# VFD-IV-26-T3-5x7.net
KiCad netlist of a schematic drawn in EAGLE
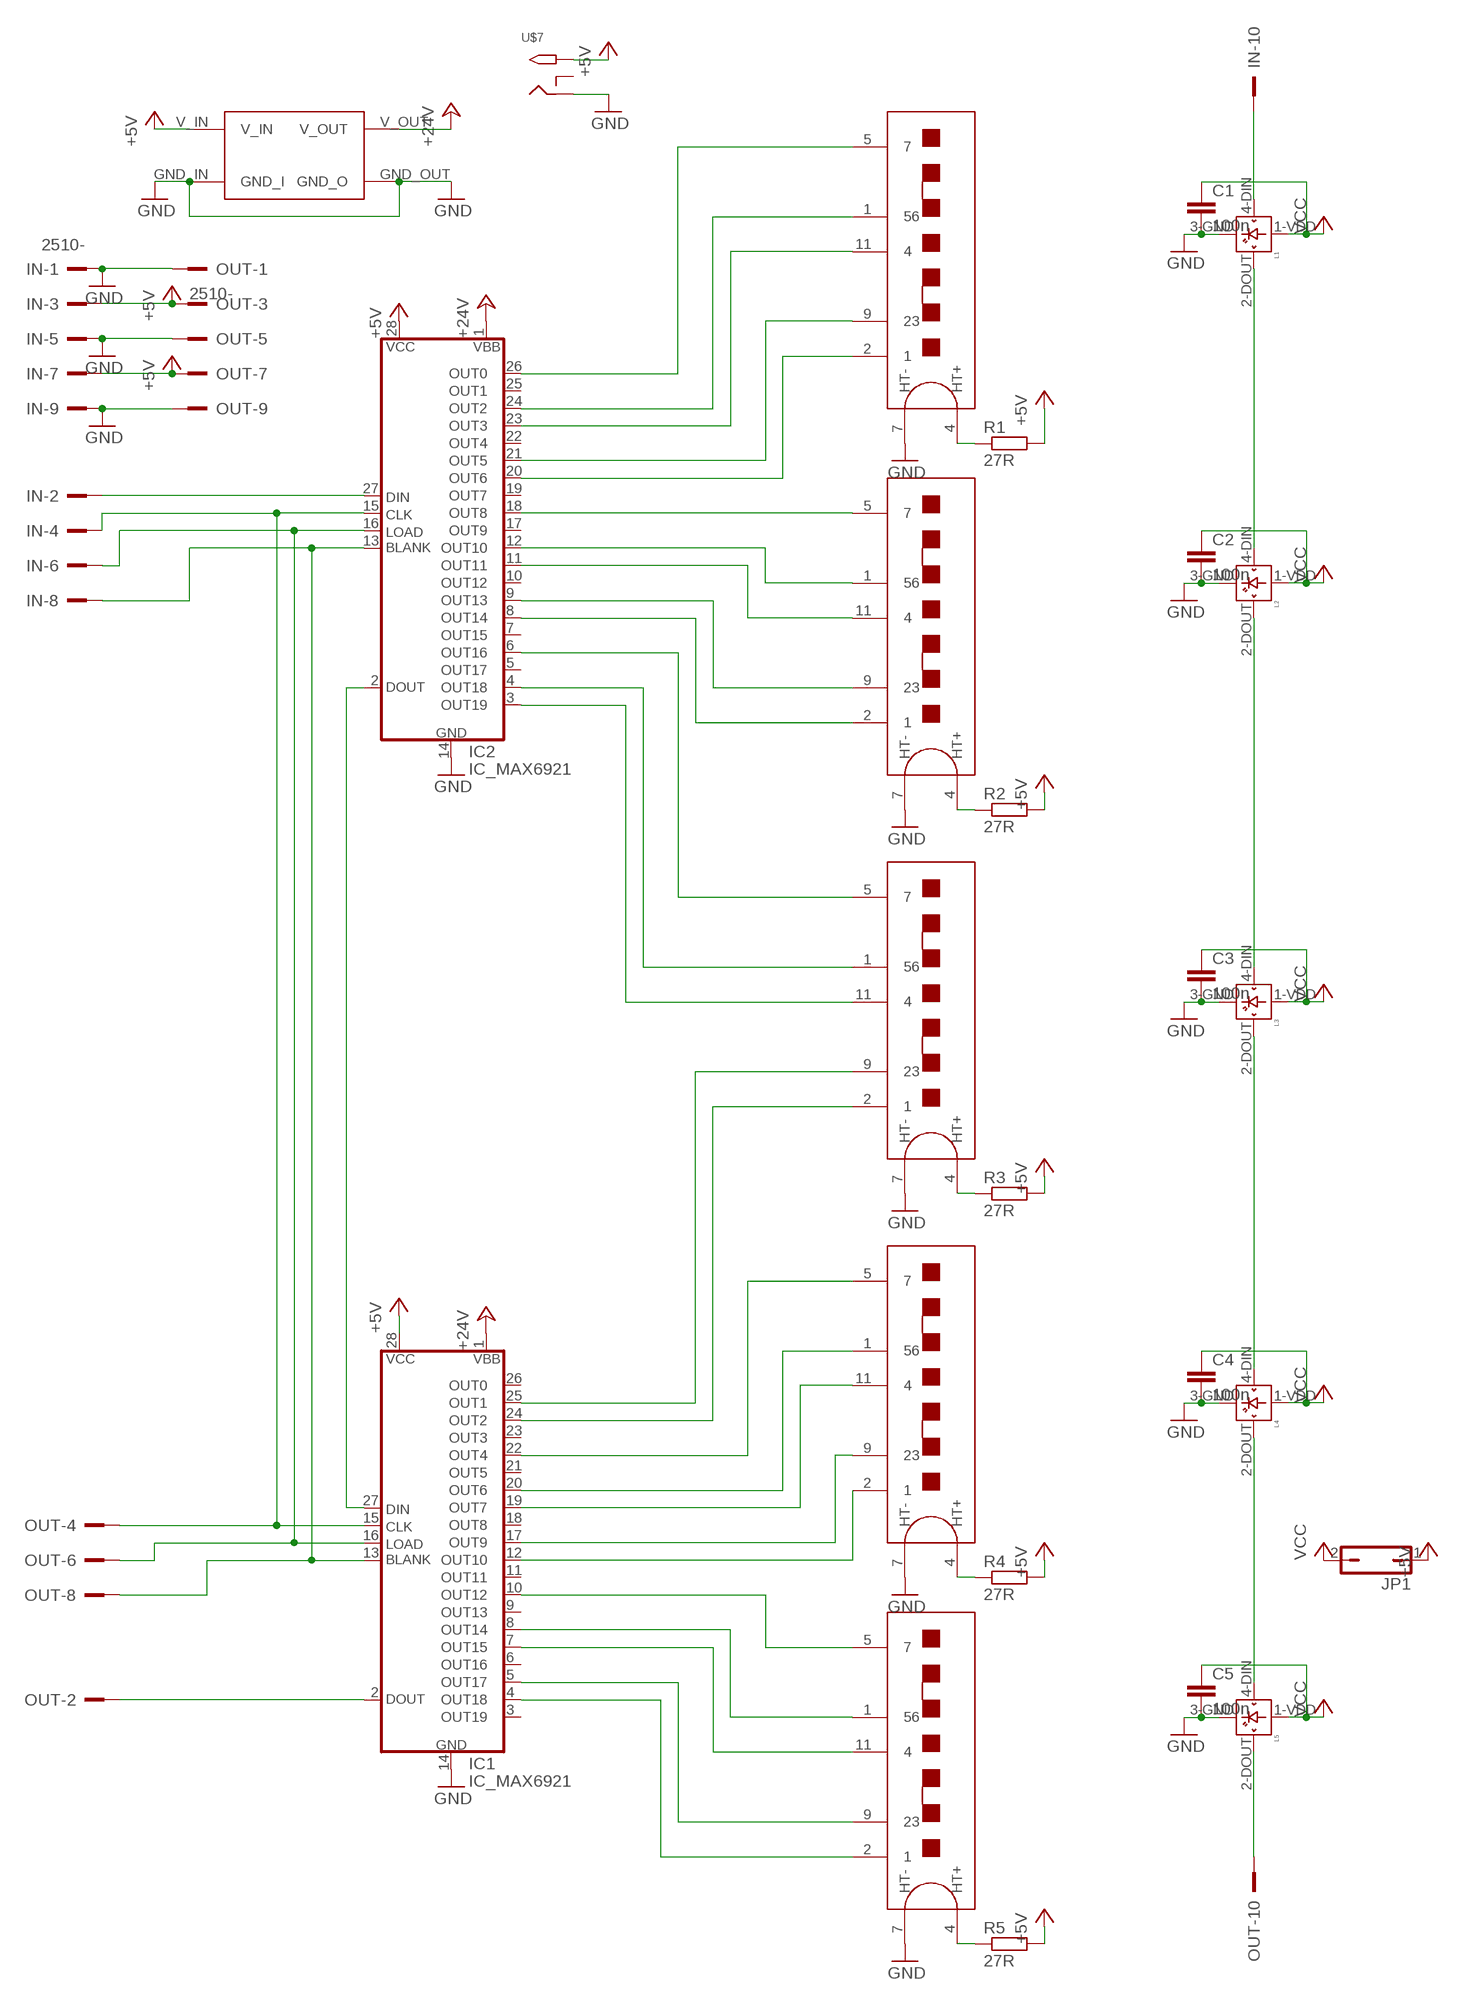
[diagram p0: schematic, sheet 1]

(export (version "E")
  (design (tool "Eeschema 10.0.6"))
  (components
    (comp (ref "1")
      (value "IV-26-T3_DISP")
      (footprint "eagle-import:IV-26_T2_T3")
      (libsource (lib "eagle-import") (part "IV-26-T3_DISP"))
    )
    (comp (ref "2")
      (value "IV-26-T3_DISP")
      (footprint "eagle-import:IV-26_T2_T3")
      (libsource (lib "eagle-import") (part "IV-26-T3_DISP"))
    )
    (comp (ref "3")
      (value "IV-26-T3_DISP")
      (footprint "eagle-import:IV-26_T2_T3")
      (libsource (lib "eagle-import") (part "IV-26-T3_DISP"))
    )
    (comp (ref "4")
      (value "IV-26-T3_DISP")
      (footprint "eagle-import:IV-26_T2_T3")
      (libsource (lib "eagle-import") (part "IV-26-T3_DISP"))
    )
    (comp (ref "5")
      (value "IV-26-T3_DISP")
      (footprint "eagle-import:IV-26_T2_T3")
      (libsource (lib "eagle-import") (part "IV-26-T3_DISP"))
    )
    (comp (ref "C1")
      (value "100n")
      (footprint "eagle-import:C050-025X075")
      (libsource (lib "eagle-import") (part "C-EU050-025X075"))
    )
    (comp (ref "C2")
      (value "100n")
      (footprint "eagle-import:C050-025X075")
      (libsource (lib "eagle-import") (part "C-EU050-025X075"))
    )
    (comp (ref "C3")
      (value "100n")
      (footprint "eagle-import:C050-025X075")
      (libsource (lib "eagle-import") (part "C-EU050-025X075"))
    )
    (comp (ref "C4")
      (value "100n")
      (footprint "eagle-import:C050-025X075")
      (libsource (lib "eagle-import") (part "C-EU050-025X075"))
    )
    (comp (ref "C5")
      (value "100n")
      (footprint "eagle-import:C050-025X075")
      (libsource (lib "eagle-import") (part "C-EU050-025X075"))
    )
    (comp (ref "IC1")
      (value "IC_MAX6921")
      (footprint "eagle-import:S28")
      (libsource (lib "eagle-import") (part "IC_MAX6921"))
    )
    (comp (ref "IC2")
      (value "IC_MAX6921")
      (footprint "eagle-import:S28")
      (libsource (lib "eagle-import") (part "IC_MAX6921"))
    )
    (comp (ref "IN")
      (value "2510-")
      (footprint "eagle-import:PAK100_2500-10")
      (fields (field (name "MF") "3M") (field (name "MPN") "2510-6002UB"))
      (libsource (lib "eagle-import") (part "2510-"))
    )
    (comp (ref "JP1")
      (value "JP1Q")
      (footprint "eagle-import:JP1")
      (libsource (lib "eagle-import") (part "JP1Q"))
    )
    (comp (ref "L1")
      (value "WS2812B")
      (footprint "eagle-import:WS2812B")
      (libsource (lib "eagle-import") (part "WS2812B"))
    )
    (comp (ref "L2")
      (value "WS2812B")
      (footprint "eagle-import:WS2812B")
      (libsource (lib "eagle-import") (part "WS2812B"))
    )
    (comp (ref "L3")
      (value "WS2812B")
      (footprint "eagle-import:WS2812B")
      (libsource (lib "eagle-import") (part "WS2812B"))
    )
    (comp (ref "L4")
      (value "WS2812B")
      (footprint "eagle-import:WS2812B")
      (libsource (lib "eagle-import") (part "WS2812B"))
    )
    (comp (ref "L5")
      (value "WS2812B")
      (footprint "eagle-import:WS2812B")
      (libsource (lib "eagle-import") (part "WS2812B"))
    )
    (comp (ref "OUT")
      (value "2510-")
      (footprint "eagle-import:PAK100_2500-10")
      (fields (field (name "MF") "3M") (field (name "MPN") "2510-6002UB"))
      (libsource (lib "eagle-import") (part "2510-"))
    )
    (comp (ref "R1")
      (value "27R")
      (footprint "eagle-import:0207_10")
      (libsource (lib "eagle-import") (part "R-EU_0207/10"))
    )
    (comp (ref "R2")
      (value "27R")
      (footprint "eagle-import:0207_10")
      (libsource (lib "eagle-import") (part "R-EU_0207/10"))
    )
    (comp (ref "R3")
      (value "27R")
      (footprint "eagle-import:0207_10")
      (libsource (lib "eagle-import") (part "R-EU_0207/10"))
    )
    (comp (ref "R4")
      (value "27R")
      (footprint "eagle-import:0207_10")
      (libsource (lib "eagle-import") (part "R-EU_0207/10"))
    )
    (comp (ref "R5")
      (value "27R")
      (footprint "eagle-import:0207_10")
      (libsource (lib "eagle-import") (part "R-EU_0207/10"))
    )
    (comp (ref "U$6")
      (value "STEP_UP_MODULE")
      (footprint "eagle-import:STEP_UP_MODULE")
      (libsource (lib "eagle-import") (part "STEP_UP_MODULE"))
    )
    (comp (ref "U$7")
      (value "2.1MMJACKTHM")
      (footprint "eagle-import:PJ-102A")
      (libsource (lib "eagle-import") (part "2.1MMJACKTHM"))
    )
  )
  (nets
    (net (code "1") (name "+5V") (class "Default")
      (node (ref "IC1") (pin "28") (pinfunction "VCC_28") (pintype "power_in"))
      (node (ref "IC2") (pin "28") (pinfunction "VCC_28") (pintype "power_in"))
      (node (ref "IN") (pin "3") (pinfunction "KL_3") (pintype "passive"))
      (node (ref "IN") (pin "7") (pinfunction "KL_7") (pintype "passive"))
      (node (ref "JP1") (pin "1") (pinfunction "1_1") (pintype "passive"))
      (node (ref "OUT") (pin "3") (pinfunction "KL_3") (pintype "passive"))
      (node (ref "OUT") (pin "7") (pinfunction "KL_7") (pintype "passive"))
      (node (ref "R1") (pin "2") (pinfunction "2_2") (pintype "passive"))
      (node (ref "R2") (pin "2") (pinfunction "2_2") (pintype "passive"))
      (node (ref "R3") (pin "2") (pinfunction "2_2") (pintype "passive"))
      (node (ref "R4") (pin "2") (pinfunction "2_2") (pintype "passive"))
      (node (ref "R5") (pin "2") (pinfunction "2_2") (pintype "passive"))
      (node (ref "U$6") (pin "V_IN") (pinfunction "V_IN_V_IN") (pintype "power_in"))
      (node (ref "U$7") (pin "TIP") (pinfunction "TIP_TIP") (pintype "bidirectional"))
    )
    (net (code "2") (name "+24V") (class "Default")
      (node (ref "IC1") (pin "1") (pinfunction "VBB_1") (pintype "power_in"))
      (node (ref "IC2") (pin "1") (pinfunction "VBB_1") (pintype "power_in"))
      (node (ref "U$6") (pin "V_OUT") (pinfunction "V_OUT_V_OUT") (pintype "power_in"))
    )
    (net (code "3") (name "GND") (class "Default")
      (node (ref "1") (pin "7") (pinfunction "HT-_7") (pintype "power_in"))
      (node (ref "2") (pin "7") (pinfunction "HT-_7") (pintype "power_in"))
      (node (ref "3") (pin "7") (pinfunction "HT-_7") (pintype "power_in"))
      (node (ref "4") (pin "7") (pinfunction "HT-_7") (pintype "power_in"))
      (node (ref "5") (pin "7") (pinfunction "HT-_7") (pintype "power_in"))
      (node (ref "C1") (pin "2") (pinfunction "2_2") (pintype "passive"))
      (node (ref "C2") (pin "2") (pinfunction "2_2") (pintype "passive"))
      (node (ref "C3") (pin "2") (pinfunction "2_2") (pintype "passive"))
      (node (ref "C4") (pin "2") (pinfunction "2_2") (pintype "passive"))
      (node (ref "C5") (pin "2") (pinfunction "2_2") (pintype "passive"))
      (node (ref "IC1") (pin "14") (pinfunction "GND_14") (pintype "power_in"))
      (node (ref "IC2") (pin "14") (pinfunction "GND_14") (pintype "power_in"))
      (node (ref "IN") (pin "1") (pinfunction "KL_1") (pintype "passive"))
      (node (ref "IN") (pin "5") (pinfunction "KL_5") (pintype "passive"))
      (node (ref "IN") (pin "9") (pinfunction "KL_9") (pintype "passive"))
      (node (ref "L1") (pin "3-GND") (pinfunction "GND_3-GND") (pintype "bidirectional"))
      (node (ref "L2") (pin "3-GND") (pinfunction "GND_3-GND") (pintype "bidirectional"))
      (node (ref "L3") (pin "3-GND") (pinfunction "GND_3-GND") (pintype "bidirectional"))
      (node (ref "L4") (pin "3-GND") (pinfunction "GND_3-GND") (pintype "bidirectional"))
      (node (ref "L5") (pin "3-GND") (pinfunction "GND_3-GND") (pintype "bidirectional"))
      (node (ref "OUT") (pin "1") (pinfunction "KL_1") (pintype "passive"))
      (node (ref "OUT") (pin "5") (pinfunction "KL_5") (pintype "passive"))
      (node (ref "OUT") (pin "9") (pinfunction "KL_9") (pintype "passive"))
      (node (ref "U$6") (pin "GND_IN") (pinfunction "GND_I_GND_IN") (pintype "power_in"))
      (node (ref "U$6") (pin "GND_OUT") (pinfunction "GND_O_GND_OUT") (pintype "power_in"))
      (node (ref "U$7") (pin "RING") (pinfunction "RING_RING") (pintype "bidirectional"))
    )
    (net (code "4") (name "Net-(1-1)") (class "Default")
      (node (ref "1") (pin "2") (pinfunction "1_2") (pintype "input"))
      (node (ref "IC2") (pin "20") (pinfunction "OUT6_20") (pintype "output"))
    )
    (net (code "5") (name "Net-(1-4)") (class "Default")
      (node (ref "1") (pin "11") (pinfunction "4_11") (pintype "input"))
      (node (ref "IC2") (pin "23") (pinfunction "OUT3_23") (pintype "output"))
    )
    (net (code "6") (name "Net-(1-7)") (class "Default")
      (node (ref "1") (pin "5") (pinfunction "7_5") (pintype "input"))
      (node (ref "IC2") (pin "26") (pinfunction "OUT0_26") (pintype "output"))
    )
    (net (code "7") (name "Net-(1-23)") (class "Default")
      (node (ref "1") (pin "9") (pinfunction "23_9") (pintype "input"))
      (node (ref "IC2") (pin "21") (pinfunction "OUT5_21") (pintype "output"))
    )
    (net (code "8") (name "Net-(1-56)") (class "Default")
      (node (ref "1") (pin "1") (pinfunction "56_1") (pintype "input"))
      (node (ref "IC2") (pin "24") (pinfunction "OUT2_24") (pintype "output"))
    )
    (net (code "9") (name "Net-(1-HT+)") (class "Default")
      (node (ref "1") (pin "4") (pinfunction "HT+_4") (pintype "power_in"))
      (node (ref "R1") (pin "1") (pinfunction "1_1") (pintype "passive"))
    )
    (net (code "10") (name "Net-(2-1)") (class "Default")
      (node (ref "2") (pin "2") (pinfunction "1_2") (pintype "input"))
      (node (ref "IC2") (pin "8") (pinfunction "OUT14_8") (pintype "output"))
    )
    (net (code "11") (name "Net-(2-4)") (class "Default")
      (node (ref "2") (pin "11") (pinfunction "4_11") (pintype "input"))
      (node (ref "IC2") (pin "11") (pinfunction "OUT11_11") (pintype "output"))
    )
    (net (code "12") (name "Net-(2-7)") (class "Default")
      (node (ref "2") (pin "5") (pinfunction "7_5") (pintype "input"))
      (node (ref "IC2") (pin "18") (pinfunction "OUT8_18") (pintype "output"))
    )
    (net (code "13") (name "Net-(2-23)") (class "Default")
      (node (ref "2") (pin "9") (pinfunction "23_9") (pintype "input"))
      (node (ref "IC2") (pin "9") (pinfunction "OUT13_9") (pintype "output"))
    )
    (net (code "14") (name "Net-(2-56)") (class "Default")
      (node (ref "2") (pin "1") (pinfunction "56_1") (pintype "input"))
      (node (ref "IC2") (pin "12") (pinfunction "OUT10_12") (pintype "output"))
    )
    (net (code "15") (name "Net-(2-HT+)") (class "Default")
      (node (ref "2") (pin "4") (pinfunction "HT+_4") (pintype "power_in"))
      (node (ref "R2") (pin "1") (pinfunction "1_1") (pintype "passive"))
    )
    (net (code "16") (name "Net-(3-1)") (class "Default")
      (node (ref "3") (pin "2") (pinfunction "1_2") (pintype "input"))
      (node (ref "IC1") (pin "24") (pinfunction "OUT2_24") (pintype "output"))
    )
    (net (code "17") (name "Net-(3-4)") (class "Default")
      (node (ref "3") (pin "11") (pinfunction "4_11") (pintype "input"))
      (node (ref "IC2") (pin "3") (pinfunction "OUT19_3") (pintype "output"))
    )
    (net (code "18") (name "Net-(3-7)") (class "Default")
      (node (ref "3") (pin "5") (pinfunction "7_5") (pintype "input"))
      (node (ref "IC2") (pin "6") (pinfunction "OUT16_6") (pintype "output"))
    )
    (net (code "19") (name "Net-(3-23)") (class "Default")
      (node (ref "3") (pin "9") (pinfunction "23_9") (pintype "input"))
      (node (ref "IC1") (pin "25") (pinfunction "OUT1_25") (pintype "output"))
    )
    (net (code "20") (name "Net-(3-56)") (class "Default")
      (node (ref "3") (pin "1") (pinfunction "56_1") (pintype "input"))
      (node (ref "IC2") (pin "4") (pinfunction "OUT18_4") (pintype "output"))
    )
    (net (code "21") (name "Net-(3-HT+)") (class "Default")
      (node (ref "3") (pin "4") (pinfunction "HT+_4") (pintype "power_in"))
      (node (ref "R3") (pin "1") (pinfunction "1_1") (pintype "passive"))
    )
    (net (code "22") (name "Net-(4-1)") (class "Default")
      (node (ref "4") (pin "2") (pinfunction "1_2") (pintype "input"))
      (node (ref "IC1") (pin "12") (pinfunction "OUT10_12") (pintype "output"))
    )
    (net (code "23") (name "Net-(4-4)") (class "Default")
      (node (ref "4") (pin "11") (pinfunction "4_11") (pintype "input"))
      (node (ref "IC1") (pin "19") (pinfunction "OUT7_19") (pintype "output"))
    )
    (net (code "24") (name "Net-(4-7)") (class "Default")
      (node (ref "4") (pin "5") (pinfunction "7_5") (pintype "input"))
      (node (ref "IC1") (pin "22") (pinfunction "OUT4_22") (pintype "output"))
    )
    (net (code "25") (name "Net-(4-23)") (class "Default")
      (node (ref "4") (pin "9") (pinfunction "23_9") (pintype "input"))
      (node (ref "IC1") (pin "17") (pinfunction "OUT9_17") (pintype "output"))
    )
    (net (code "26") (name "Net-(4-56)") (class "Default")
      (node (ref "4") (pin "1") (pinfunction "56_1") (pintype "input"))
      (node (ref "IC1") (pin "20") (pinfunction "OUT6_20") (pintype "output"))
    )
    (net (code "27") (name "Net-(4-HT+)") (class "Default")
      (node (ref "4") (pin "4") (pinfunction "HT+_4") (pintype "power_in"))
      (node (ref "R4") (pin "1") (pinfunction "1_1") (pintype "passive"))
    )
    (net (code "28") (name "Net-(5-1)") (class "Default")
      (node (ref "5") (pin "2") (pinfunction "1_2") (pintype "input"))
      (node (ref "IC1") (pin "4") (pinfunction "OUT18_4") (pintype "output"))
    )
    (net (code "29") (name "Net-(5-4)") (class "Default")
      (node (ref "5") (pin "11") (pinfunction "4_11") (pintype "input"))
      (node (ref "IC1") (pin "7") (pinfunction "OUT15_7") (pintype "output"))
    )
    (net (code "30") (name "Net-(5-7)") (class "Default")
      (node (ref "5") (pin "5") (pinfunction "7_5") (pintype "input"))
      (node (ref "IC1") (pin "10") (pinfunction "OUT12_10") (pintype "output"))
    )
    (net (code "31") (name "Net-(5-23)") (class "Default")
      (node (ref "5") (pin "9") (pinfunction "23_9") (pintype "input"))
      (node (ref "IC1") (pin "5") (pinfunction "OUT17_5") (pintype "output"))
    )
    (net (code "32") (name "Net-(5-56)") (class "Default")
      (node (ref "5") (pin "1") (pinfunction "56_1") (pintype "input"))
      (node (ref "IC1") (pin "8") (pinfunction "OUT14_8") (pintype "output"))
    )
    (net (code "33") (name "Net-(5-HT+)") (class "Default")
      (node (ref "5") (pin "4") (pinfunction "HT+_4") (pintype "power_in"))
      (node (ref "R5") (pin "1") (pinfunction "1_1") (pintype "passive"))
    )
    (net (code "34") (name "Net-(IC1-BLANK)") (class "Default")
      (node (ref "IC1") (pin "13") (pinfunction "BLANK_13") (pintype "input"))
      (node (ref "IC2") (pin "13") (pinfunction "BLANK_13") (pintype "input"))
      (node (ref "IN") (pin "8") (pinfunction "KL_8") (pintype "passive"))
      (node (ref "OUT") (pin "8") (pinfunction "KL_8") (pintype "passive"))
    )
    (net (code "35") (name "Net-(IC1-CLK)") (class "Default")
      (node (ref "IC1") (pin "15") (pinfunction "CLK_15") (pintype "input"))
      (node (ref "IC2") (pin "15") (pinfunction "CLK_15") (pintype "input"))
      (node (ref "IN") (pin "4") (pinfunction "KL_4") (pintype "passive"))
      (node (ref "OUT") (pin "4") (pinfunction "KL_4") (pintype "passive"))
    )
    (net (code "36") (name "Net-(IC1-DIN)") (class "Default")
      (node (ref "IC1") (pin "27") (pinfunction "DIN_27") (pintype "input"))
      (node (ref "IC2") (pin "2") (pinfunction "DOUT_2") (pintype "output"))
    )
    (net (code "37") (name "Net-(IC1-DOUT)") (class "Default")
      (node (ref "IC1") (pin "2") (pinfunction "DOUT_2") (pintype "output"))
      (node (ref "OUT") (pin "2") (pinfunction "KL_2") (pintype "passive"))
    )
    (net (code "38") (name "Net-(IC1-LOAD)") (class "Default")
      (node (ref "IC1") (pin "16") (pinfunction "LOAD_16") (pintype "input"))
      (node (ref "IC2") (pin "16") (pinfunction "LOAD_16") (pintype "input"))
      (node (ref "IN") (pin "6") (pinfunction "KL_6") (pintype "passive"))
      (node (ref "OUT") (pin "6") (pinfunction "KL_6") (pintype "passive"))
    )
    (net (code "39") (name "Net-(IC2-DIN)") (class "Default")
      (node (ref "IC2") (pin "27") (pinfunction "DIN_27") (pintype "input"))
      (node (ref "IN") (pin "2") (pinfunction "KL_2") (pintype "passive"))
    )
    (net (code "40") (name "Net-(INB-KL)") (class "Default")
      (node (ref "IN") (pin "10") (pinfunction "KL_10") (pintype "passive"))
      (node (ref "L1") (pin "4-DIN") (pinfunction "DIN_4-DIN") (pintype "input"))
    )
    (net (code "41") (name "Net-(L1-DOUT)") (class "Default")
      (node (ref "L1") (pin "2-DOUT") (pinfunction "DOUT_2-DOUT") (pintype "output"))
      (node (ref "L2") (pin "4-DIN") (pinfunction "DIN_4-DIN") (pintype "input"))
    )
    (net (code "42") (name "Net-(L2-DOUT)") (class "Default")
      (node (ref "L2") (pin "2-DOUT") (pinfunction "DOUT_2-DOUT") (pintype "output"))
      (node (ref "L3") (pin "4-DIN") (pinfunction "DIN_4-DIN") (pintype "input"))
    )
    (net (code "43") (name "Net-(L3-DOUT)") (class "Default")
      (node (ref "L3") (pin "2-DOUT") (pinfunction "DOUT_2-DOUT") (pintype "output"))
      (node (ref "L4") (pin "4-DIN") (pinfunction "DIN_4-DIN") (pintype "input"))
    )
    (net (code "44") (name "Net-(L4-DOUT)") (class "Default")
      (node (ref "L4") (pin "2-DOUT") (pinfunction "DOUT_2-DOUT") (pintype "output"))
      (node (ref "L5") (pin "4-DIN") (pinfunction "DIN_4-DIN") (pintype "input"))
    )
    (net (code "45") (name "Net-(L5-DOUT)") (class "Default")
      (node (ref "L5") (pin "2-DOUT") (pinfunction "DOUT_2-DOUT") (pintype "output"))
      (node (ref "OUT") (pin "10") (pinfunction "KL_10") (pintype "passive"))
    )
    (net (code "46") (name "VCC") (class "Default")
      (node (ref "C1") (pin "1") (pinfunction "1_1") (pintype "passive"))
      (node (ref "C2") (pin "1") (pinfunction "1_1") (pintype "passive"))
      (node (ref "C3") (pin "1") (pinfunction "1_1") (pintype "passive"))
      (node (ref "C4") (pin "1") (pinfunction "1_1") (pintype "passive"))
      (node (ref "C5") (pin "1") (pinfunction "1_1") (pintype "passive"))
      (node (ref "JP1") (pin "2") (pinfunction "2_2") (pintype "passive"))
      (node (ref "L1") (pin "1-VDD") (pinfunction "VDD_1-VDD") (pintype "bidirectional"))
      (node (ref "L2") (pin "1-VDD") (pinfunction "VDD_1-VDD") (pintype "bidirectional"))
      (node (ref "L3") (pin "1-VDD") (pinfunction "VDD_1-VDD") (pintype "bidirectional"))
      (node (ref "L4") (pin "1-VDD") (pinfunction "VDD_1-VDD") (pintype "bidirectional"))
      (node (ref "L5") (pin "1-VDD") (pinfunction "VDD_1-VDD") (pintype "bidirectional"))
    )
    (net (code "47") (name "unconnected-(IC1-OUT0-Pad26)") (class "Default")
      (node (ref "IC1") (pin "26") (pinfunction "OUT0_26") (pintype "output"))
    )
    (net (code "48") (name "unconnected-(IC1-OUT3-Pad23)") (class "Default")
      (node (ref "IC1") (pin "23") (pinfunction "OUT3_23") (pintype "output"))
    )
    (net (code "49") (name "unconnected-(IC1-OUT5-Pad21)") (class "Default")
      (node (ref "IC1") (pin "21") (pinfunction "OUT5_21") (pintype "output"))
    )
    (net (code "50") (name "unconnected-(IC1-OUT8-Pad18)") (class "Default")
      (node (ref "IC1") (pin "18") (pinfunction "OUT8_18") (pintype "output"))
    )
    (net (code "51") (name "unconnected-(IC1-OUT11-Pad11)") (class "Default")
      (node (ref "IC1") (pin "11") (pinfunction "OUT11_11") (pintype "output"))
    )
    (net (code "52") (name "unconnected-(IC1-OUT13-Pad9)") (class "Default")
      (node (ref "IC1") (pin "9") (pinfunction "OUT13_9") (pintype "output"))
    )
    (net (code "53") (name "unconnected-(IC1-OUT16-Pad6)") (class "Default")
      (node (ref "IC1") (pin "6") (pinfunction "OUT16_6") (pintype "output"))
    )
    (net (code "54") (name "unconnected-(IC1-OUT19-Pad3)") (class "Default")
      (node (ref "IC1") (pin "3") (pinfunction "OUT19_3") (pintype "output"))
    )
    (net (code "55") (name "unconnected-(IC2-OUT1-Pad25)") (class "Default")
      (node (ref "IC2") (pin "25") (pinfunction "OUT1_25") (pintype "output"))
    )
    (net (code "56") (name "unconnected-(IC2-OUT4-Pad22)") (class "Default")
      (node (ref "IC2") (pin "22") (pinfunction "OUT4_22") (pintype "output"))
    )
    (net (code "57") (name "unconnected-(IC2-OUT7-Pad19)") (class "Default")
      (node (ref "IC2") (pin "19") (pinfunction "OUT7_19") (pintype "output"))
    )
    (net (code "58") (name "unconnected-(IC2-OUT9-Pad17)") (class "Default")
      (node (ref "IC2") (pin "17") (pinfunction "OUT9_17") (pintype "output"))
    )
    (net (code "59") (name "unconnected-(IC2-OUT12-Pad10)") (class "Default")
      (node (ref "IC2") (pin "10") (pinfunction "OUT12_10") (pintype "output"))
    )
    (net (code "60") (name "unconnected-(IC2-OUT15-Pad7)") (class "Default")
      (node (ref "IC2") (pin "7") (pinfunction "OUT15_7") (pintype "output"))
    )
    (net (code "61") (name "unconnected-(IC2-OUT17-Pad5)") (class "Default")
      (node (ref "IC2") (pin "5") (pinfunction "OUT17_5") (pintype "output"))
    )
    (net (code "62") (name "unconnected-(U$7-PadRING_SW)") (class "Default")
      (node (ref "U$7") (pin "RING_SW") (pinfunction "RING_SW_RING_SW") (pintype "bidirectional"))
    )
  )
)
